# SUPERHOOP.net
KiCad netlist of a schematic drawn in EAGLE
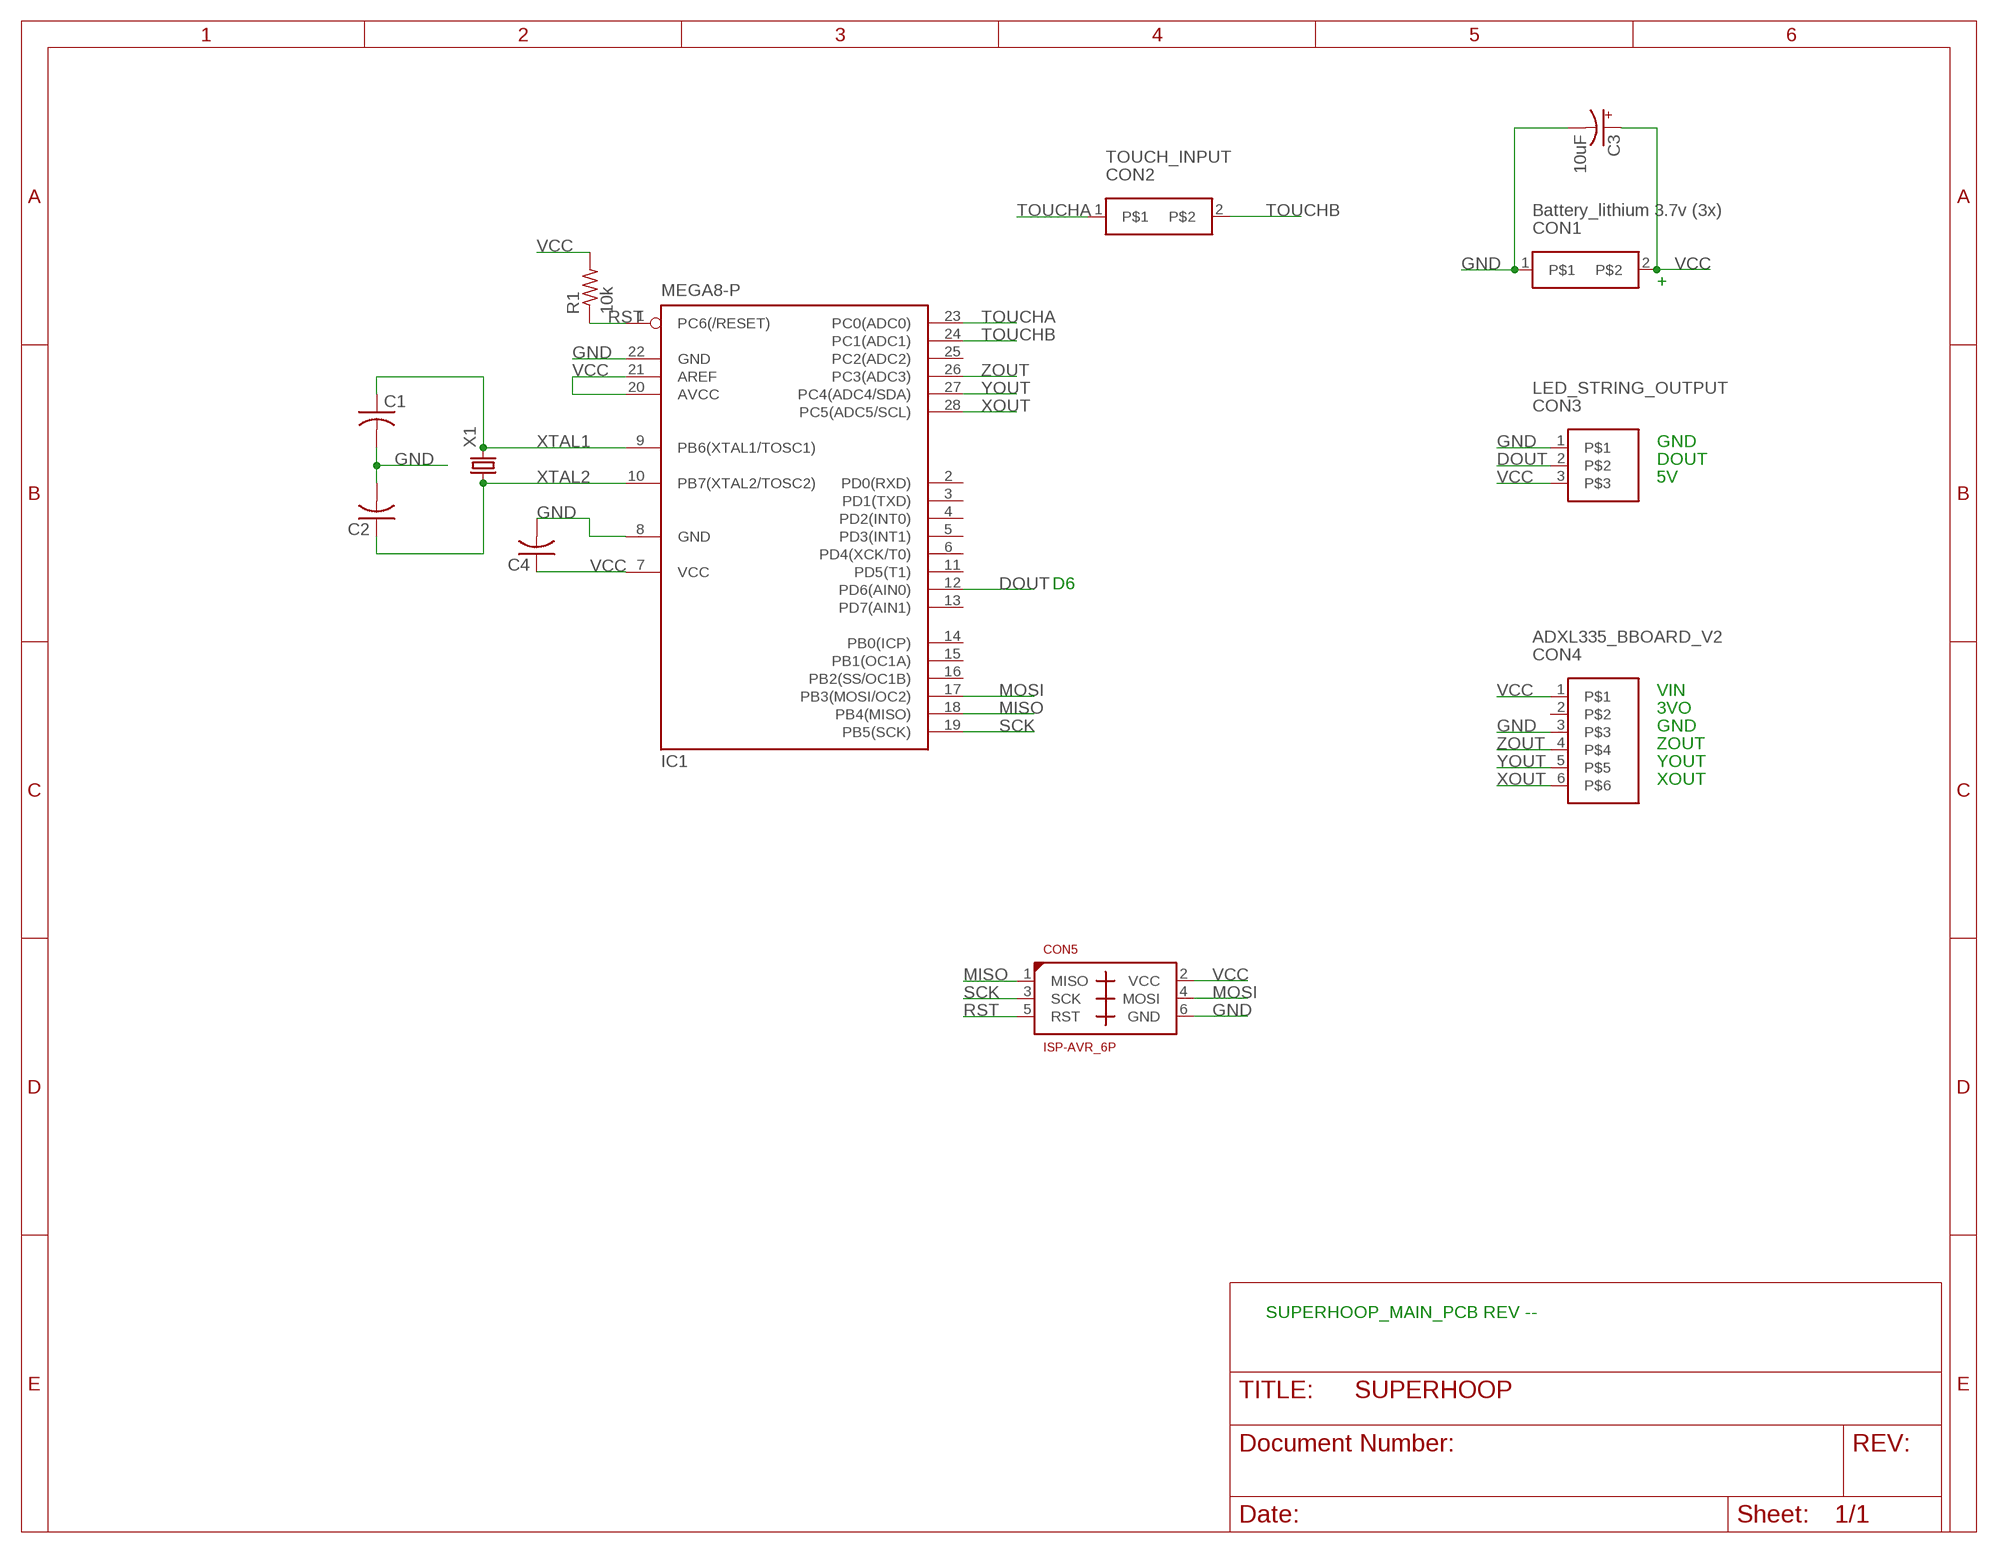
[diagram p0: schematic, sheet 1]

(export (version "E")
  (design (tool "Eeschema 10.0.6"))
  (components
    (comp (ref "C1")
      (value "C-US025-024X044")
      (footprint "eagle-import:C025-024X044")
      (libsource (lib "eagle-import") (part "C-US025-024X044"))
    )
    (comp (ref "C2")
      (value "C-US025-024X044")
      (footprint "eagle-import:C025-024X044")
      (libsource (lib "eagle-import") (part "C-US025-024X044"))
    )
    (comp (ref "C3")
      (value "10uF")
      (footprint "eagle-import:E2,5-5")
      (libsource (lib "eagle-import") (part "CPOL-USE2.5-5"))
    )
    (comp (ref "C4")
      (value "C-US025-024X044")
      (footprint "eagle-import:C025-024X044")
      (libsource (lib "eagle-import") (part "C-US025-024X044"))
    )
    (comp (ref "CON1")
      (value "Battery_lithium 3.7v (3x)")
      (footprint "eagle-import:HEADER_2X1_2.54")
      (libsource (lib "eagle-import") (part "HEADER_2X1_2.54"))
    )
    (comp (ref "CON2")
      (value "TOUCH_INPUT")
      (footprint "eagle-import:HEADER_2X1_2.54")
      (libsource (lib "eagle-import") (part "HEADER_2X1_2.54"))
    )
    (comp (ref "CON3")
      (value "LED_STRING_OUTPUT")
      (footprint "eagle-import:HEADER_3X1_2.54")
      (libsource (lib "eagle-import") (part "HEADER_3X1"))
    )
    (comp (ref "CON4")
      (value "ADXL335_BBOARD_V2")
      (footprint "eagle-import:HEADER_6X1_2.54")
      (libsource (lib "eagle-import") (part "HEADER_6X1_2.54"))
    )
    (comp (ref "CON5")
      (value "ISP-AVR_6P")
      (footprint "eagle-import:HEADER_3X2_2.54")
      (libsource (lib "eagle-import") (part "ISP-AVR_6P"))
    )
    (comp (ref "IC1")
      (value "MEGA8-P")
      (footprint "eagle-import:DIL28-3")
      (libsource (lib "eagle-import") (part "MEGA8-P"))
    )
    (comp (ref "R1")
      (value "10k")
      (footprint "eagle-import:0207_12")
      (libsource (lib "eagle-import") (part "R-US_0207/12"))
    )
    (comp (ref "X1")
      (value "CRYSTALHC49S")
      (footprint "eagle-import:HC49_S")
      (libsource (lib "eagle-import") (part "CRYSTALHC49S"))
    )
  )
  (nets
    (net (code "1") (name "/DOUT") (class "Default")
      (node (ref "CON3") (pin "2") (pinfunction "P$2_2") (pintype "bidirectional"))
      (node (ref "IC1") (pin "12") (pinfunction "PD6(AIN0)_12") (pintype "bidirectional"))
    )
    (net (code "2") (name "/GND") (class "Default")
      (node (ref "C1") (pin "2") (pinfunction "2_2") (pintype "passive"))
      (node (ref "C2") (pin "2") (pinfunction "2_2") (pintype "passive"))
      (node (ref "C3") (pin "-") (pinfunction "-_-") (pintype "passive"))
      (node (ref "C4") (pin "2") (pinfunction "2_2") (pintype "passive"))
      (node (ref "CON1") (pin "1") (pinfunction "P$1_1") (pintype "bidirectional"))
      (node (ref "CON3") (pin "1") (pinfunction "P$1_1") (pintype "bidirectional"))
      (node (ref "CON4") (pin "3") (pinfunction "P$3_3") (pintype "bidirectional"))
      (node (ref "CON5") (pin "6") (pinfunction "GND_6") (pintype "power_in"))
      (node (ref "IC1") (pin "22") (pinfunction "GND_22") (pintype "power_in"))
      (node (ref "IC1") (pin "8") (pinfunction "GND_8") (pintype "power_in"))
    )
    (net (code "3") (name "/MISO") (class "Default")
      (node (ref "CON5") (pin "1") (pinfunction "MISO_1") (pintype "bidirectional"))
      (node (ref "IC1") (pin "18") (pinfunction "PB4(MISO)_18") (pintype "bidirectional"))
    )
    (net (code "4") (name "/MOSI") (class "Default")
      (node (ref "CON5") (pin "4") (pinfunction "MOSI_4") (pintype "bidirectional"))
      (node (ref "IC1") (pin "17") (pinfunction "PB3(MOSI/OC2)_17") (pintype "bidirectional"))
    )
    (net (code "5") (name "/RST") (class "Default")
      (node (ref "CON5") (pin "5") (pinfunction "RST_5") (pintype "bidirectional"))
      (node (ref "IC1") (pin "1") (pinfunction "PC6(/RESET)_1") (pintype "bidirectional"))
      (node (ref "R1") (pin "1") (pinfunction "1_1") (pintype "passive"))
    )
    (net (code "6") (name "/SCK") (class "Default")
      (node (ref "CON5") (pin "3") (pinfunction "SCK_3") (pintype "bidirectional"))
      (node (ref "IC1") (pin "19") (pinfunction "PB5(SCK)_19") (pintype "bidirectional"))
    )
    (net (code "7") (name "/TOUCHA") (class "Default")
      (node (ref "CON2") (pin "1") (pinfunction "P$1_1") (pintype "bidirectional"))
      (node (ref "IC1") (pin "23") (pinfunction "PC0(ADC0)_23") (pintype "bidirectional"))
    )
    (net (code "8") (name "/TOUCHB") (class "Default")
      (node (ref "CON2") (pin "2") (pinfunction "P$2_2") (pintype "bidirectional"))
      (node (ref "IC1") (pin "24") (pinfunction "PC1(ADC1)_24") (pintype "bidirectional"))
    )
    (net (code "9") (name "/VCC") (class "Default")
      (node (ref "C3") (pin "+") (pinfunction "+_+") (pintype "passive"))
      (node (ref "C4") (pin "1") (pinfunction "1_1") (pintype "passive"))
      (node (ref "CON1") (pin "2") (pinfunction "P$2_2") (pintype "bidirectional"))
      (node (ref "CON3") (pin "3") (pinfunction "P$3_3") (pintype "bidirectional"))
      (node (ref "CON4") (pin "1") (pinfunction "P$1_1") (pintype "bidirectional"))
      (node (ref "CON5") (pin "2") (pinfunction "VCC_2") (pintype "power_in"))
      (node (ref "IC1") (pin "20") (pinfunction "AVCC_20") (pintype "power_in"))
      (node (ref "IC1") (pin "21") (pinfunction "AREF_21") (pintype "passive"))
      (node (ref "IC1") (pin "7") (pinfunction "VCC_7") (pintype "power_in"))
      (node (ref "R1") (pin "2") (pinfunction "2_2") (pintype "passive"))
    )
    (net (code "10") (name "/XOUT") (class "Default")
      (node (ref "CON4") (pin "6") (pinfunction "P$6_6") (pintype "bidirectional"))
      (node (ref "IC1") (pin "28") (pinfunction "PC5(ADC5/SCL)_28") (pintype "bidirectional"))
    )
    (net (code "11") (name "/XTAL1") (class "Default")
      (node (ref "C1") (pin "1") (pinfunction "1_1") (pintype "passive"))
      (node (ref "IC1") (pin "9") (pinfunction "PB6(XTAL1/TOSC1)_9") (pintype "bidirectional"))
      (node (ref "X1") (pin "2") (pinfunction "2_2") (pintype "passive"))
    )
    (net (code "12") (name "/XTAL2") (class "Default")
      (node (ref "C2") (pin "1") (pinfunction "1_1") (pintype "passive"))
      (node (ref "IC1") (pin "10") (pinfunction "PB7(XTAL2/TOSC2)_10") (pintype "bidirectional"))
      (node (ref "X1") (pin "1") (pinfunction "1_1") (pintype "passive"))
    )
    (net (code "13") (name "/YOUT") (class "Default")
      (node (ref "CON4") (pin "5") (pinfunction "P$5_5") (pintype "bidirectional"))
      (node (ref "IC1") (pin "27") (pinfunction "PC4(ADC4/SDA)_27") (pintype "bidirectional"))
    )
    (net (code "14") (name "/ZOUT") (class "Default")
      (node (ref "CON4") (pin "4") (pinfunction "P$4_4") (pintype "bidirectional"))
      (node (ref "IC1") (pin "26") (pinfunction "PC3(ADC3)_26") (pintype "bidirectional"))
    )
    (net (code "15") (name "unconnected-(CON4-P$2-Pad2)") (class "Default")
      (node (ref "CON4") (pin "2") (pinfunction "P$2_2") (pintype "bidirectional"))
    )
    (net (code "16") (name "unconnected-(IC1-PB0(ICP)-Pad14)") (class "Default")
      (node (ref "IC1") (pin "14") (pinfunction "PB0(ICP)_14") (pintype "bidirectional"))
    )
    (net (code "17") (name "unconnected-(IC1-PB1(OC1A)-Pad15)") (class "Default")
      (node (ref "IC1") (pin "15") (pinfunction "PB1(OC1A)_15") (pintype "bidirectional"))
    )
    (net (code "18") (name "unconnected-(IC1-PB2(SS{slash}OC1B)-Pad16)") (class "Default")
      (node (ref "IC1") (pin "16") (pinfunction "PB2(SS/OC1B)_16") (pintype "bidirectional"))
    )
    (net (code "19") (name "unconnected-(IC1-PC2(ADC2)-Pad25)") (class "Default")
      (node (ref "IC1") (pin "25") (pinfunction "PC2(ADC2)_25") (pintype "bidirectional"))
    )
    (net (code "20") (name "unconnected-(IC1-PD0(RXD)-Pad2)") (class "Default")
      (node (ref "IC1") (pin "2") (pinfunction "PD0(RXD)_2") (pintype "bidirectional"))
    )
    (net (code "21") (name "unconnected-(IC1-PD1(TXD)-Pad3)") (class "Default")
      (node (ref "IC1") (pin "3") (pinfunction "PD1(TXD)_3") (pintype "bidirectional"))
    )
    (net (code "22") (name "unconnected-(IC1-PD2(INT0)-Pad4)") (class "Default")
      (node (ref "IC1") (pin "4") (pinfunction "PD2(INT0)_4") (pintype "bidirectional"))
    )
    (net (code "23") (name "unconnected-(IC1-PD3(INT1)-Pad5)") (class "Default")
      (node (ref "IC1") (pin "5") (pinfunction "PD3(INT1)_5") (pintype "bidirectional"))
    )
    (net (code "24") (name "unconnected-(IC1-PD4(XCK{slash}T0)-Pad6)") (class "Default")
      (node (ref "IC1") (pin "6") (pinfunction "PD4(XCK/T0)_6") (pintype "bidirectional"))
    )
    (net (code "25") (name "unconnected-(IC1-PD5(T1)-Pad11)") (class "Default")
      (node (ref "IC1") (pin "11") (pinfunction "PD5(T1)_11") (pintype "bidirectional"))
    )
    (net (code "26") (name "unconnected-(IC1-PD7(AIN1)-Pad13)") (class "Default")
      (node (ref "IC1") (pin "13") (pinfunction "PD7(AIN1)_13") (pintype "bidirectional"))
    )
  )
)
